# holo_clock_1_l293_rotate_90.net
KiCad netlist of a schematic drawn in EAGLE
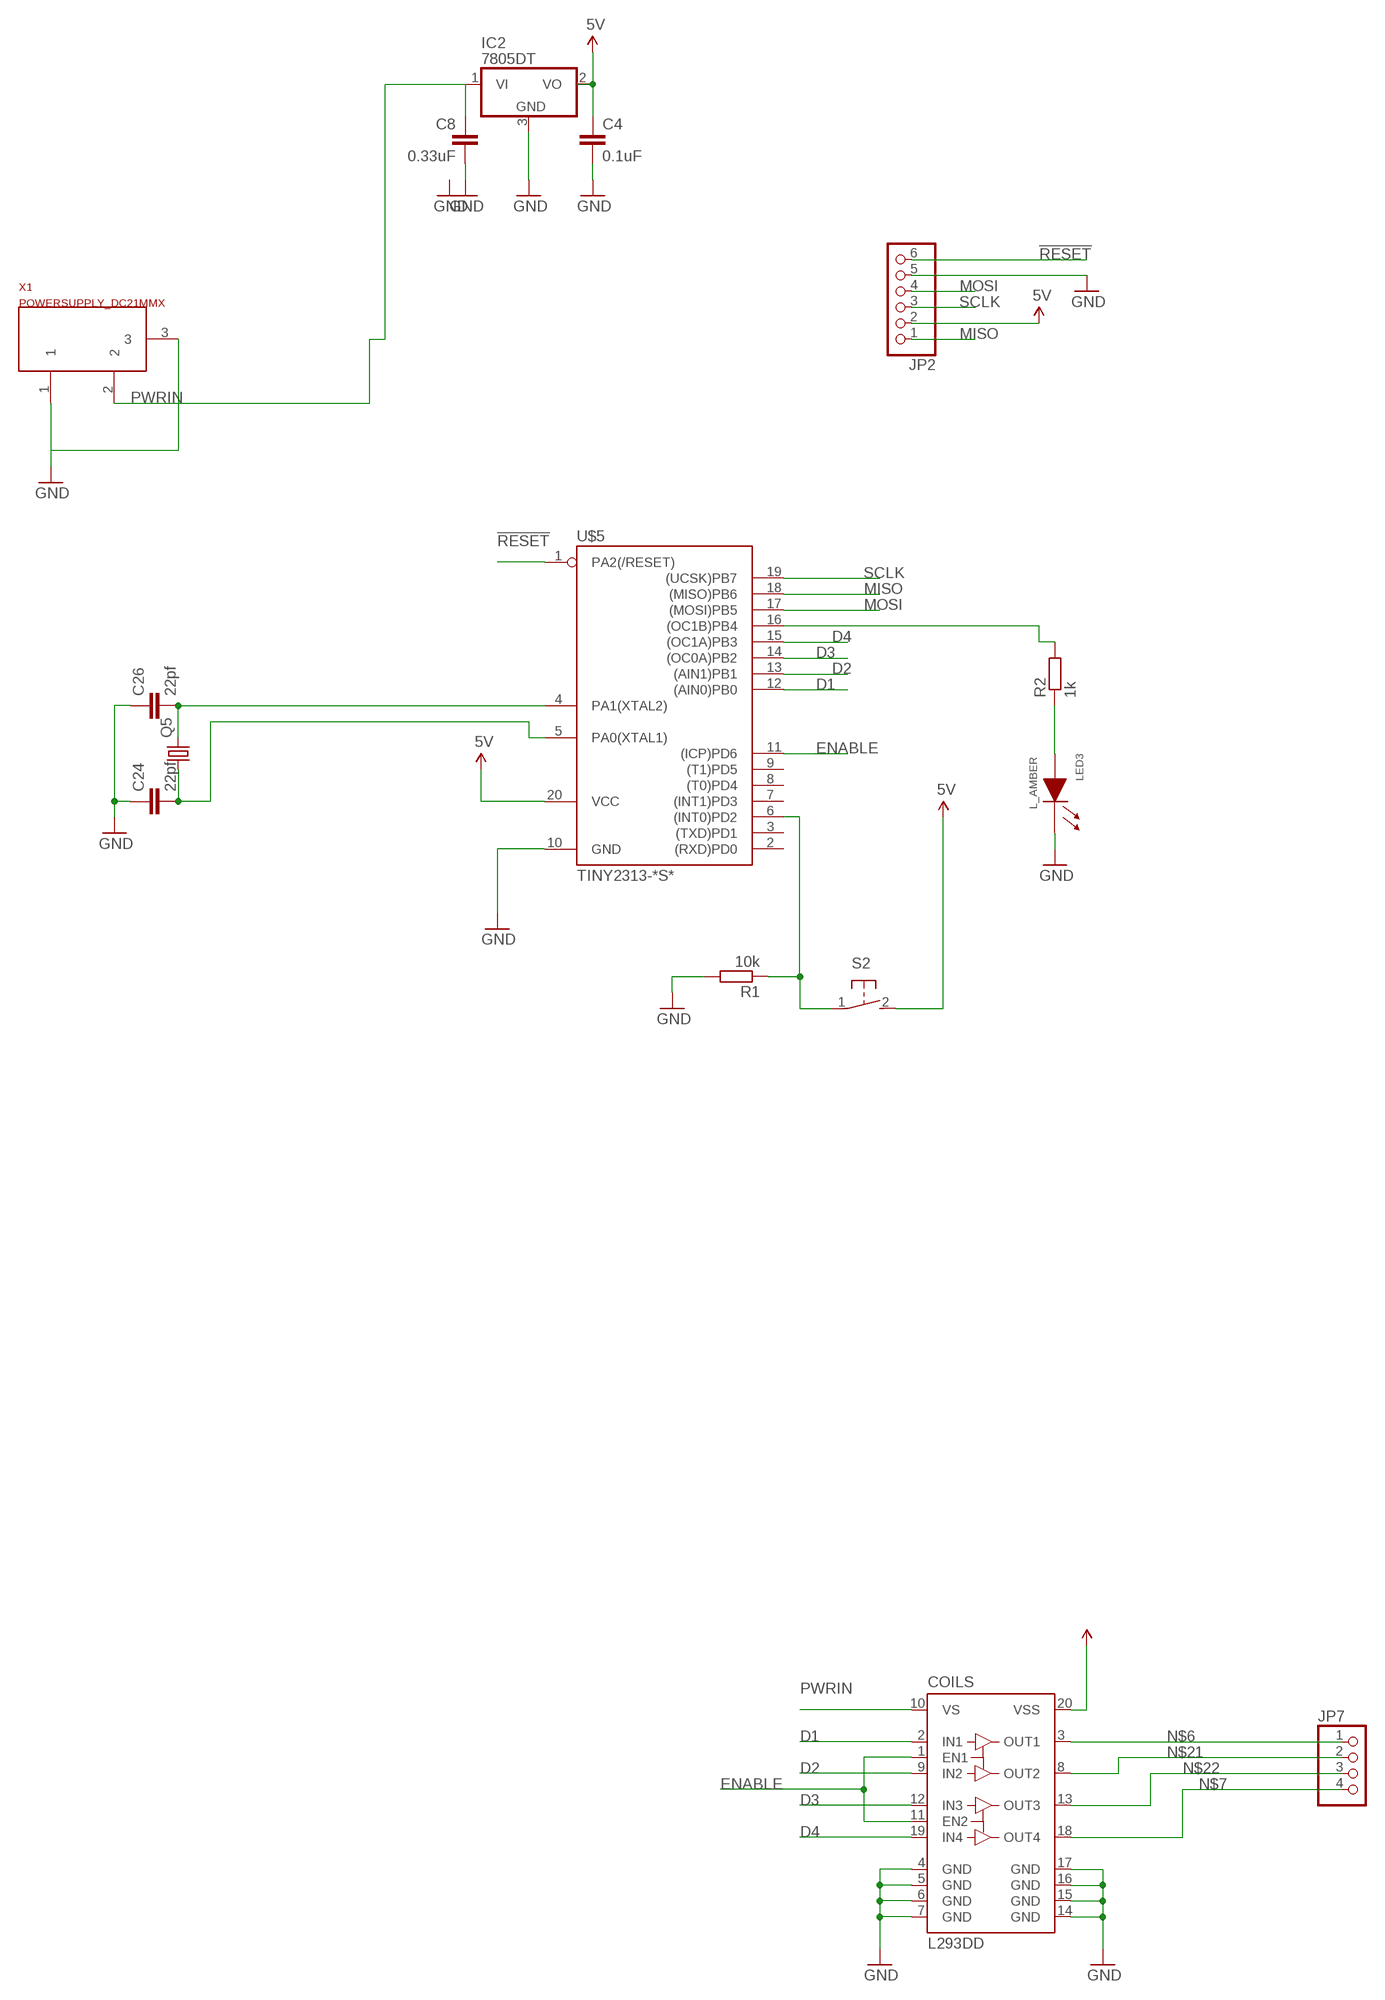
[diagram p0: schematic, sheet 1]

(export (version "E")
  (design (tool "Eeschema 10.0.6"))
  (components
    (comp (ref "C4")
      (value "0.1uF")
      (footprint "eagle-import:CAP-PTH-SMALL2")
      (libsource (lib "eagle-import") (part "CAPPTH2"))
    )
    (comp (ref "C8")
      (value "0.33uF")
      (footprint "eagle-import:CAP-PTH-SMALL2")
      (libsource (lib "eagle-import") (part "CAPPTH2"))
    )
    (comp (ref "C24")
      (value "22pf")
      (footprint "eagle-import:0805")
      (libsource (lib "eagle-import") (part "CAP0805"))
    )
    (comp (ref "C26")
      (value "22pf")
      (footprint "eagle-import:0805")
      (libsource (lib "eagle-import") (part "CAP0805"))
    )
    (comp (ref "COILS")
      (value "L293DD")
      (footprint "eagle-import:SO20")
      (libsource (lib "eagle-import") (part "L293DD"))
    )
    (comp (ref "IC2")
      (value "7805DT")
      (footprint "eagle-import:TO252")
      (libsource (lib "eagle-import") (part "78DT05"))
    )
    (comp (ref "JP2")
      (value "PINHD-1X6")
      (footprint "eagle-import:1X06")
      (libsource (lib "eagle-import") (part "PINHD-1X6"))
    )
    (comp (ref "JP7")
      (value "PINHD-1X04_2.54")
      (footprint "eagle-import:1X04")
      (libsource (lib "eagle-import") (part "PINHD-1X04_2.54"))
    )
    (comp (ref "LED3")
      (value "L_AMBER")
      (footprint "eagle-import:LED0805")
      (libsource (lib "eagle-import") (part "LED0805"))
    )
    (comp (ref "Q5")
      (value "CRYSTALHC49S")
      (footprint "eagle-import:HC49_S")
      (libsource (lib "eagle-import") (part "CRYSTALHC49S"))
    )
    (comp (ref "R1")
      (value "10k")
      (footprint "eagle-import:R0805")
      (libsource (lib "eagle-import") (part "R-EU_R0805"))
    )
    (comp (ref "R2")
      (value "1k")
      (footprint "eagle-import:R0805")
      (libsource (lib "eagle-import") (part "R-EU_R0805"))
    )
    (comp (ref "S2")
      (value "31-XX")
      (footprint "eagle-import:B3F-31XX")
      (fields (field (name "MPN") "B3F-3100"))
      (libsource (lib "eagle-import") (part "31-XX"))
    )
    (comp (ref "U$5")
      (value "TINY2313-*S*")
      (footprint "eagle-import:SO20L$")
      (libsource (lib "eagle-import") (part "TINY2313-S"))
    )
    (comp (ref "X1")
      (value "POWERSUPPLY_DC21MMX")
      (footprint "eagle-import:POWERSUPPLY_DC-21MM")
      (libsource (lib "eagle-import") (part "POWERSUPPLY_DC21MMX"))
    )
  )
  (nets
    (net (code "1") (name "/D1") (class "Default")
      (node (ref "COILS") (pin "2") (pinfunction "IN1_2") (pintype "input"))
      (node (ref "U$5") (pin "12") (pinfunction "(AIN0)PB0_12") (pintype "bidirectional"))
    )
    (net (code "2") (name "/D2") (class "Default")
      (node (ref "COILS") (pin "9") (pinfunction "IN2_9") (pintype "input"))
      (node (ref "U$5") (pin "13") (pinfunction "(AIN1)PB1_13") (pintype "bidirectional"))
    )
    (net (code "3") (name "/D3") (class "Default")
      (node (ref "COILS") (pin "12") (pinfunction "IN3_12") (pintype "input"))
      (node (ref "U$5") (pin "14") (pinfunction "(OC0A)PB2_14") (pintype "bidirectional"))
    )
    (net (code "4") (name "/D4") (class "Default")
      (node (ref "COILS") (pin "19") (pinfunction "IN4_19") (pintype "input"))
      (node (ref "U$5") (pin "15") (pinfunction "(OC1A)PB3_15") (pintype "bidirectional"))
    )
    (net (code "5") (name "/ENABLE") (class "Default")
      (node (ref "COILS") (pin "1") (pinfunction "EN1_1") (pintype "input"))
      (node (ref "COILS") (pin "11") (pinfunction "EN2_11") (pintype "input"))
      (node (ref "U$5") (pin "11") (pinfunction "(ICP)PD6_11") (pintype "bidirectional"))
    )
    (net (code "6") (name "/MISO") (class "Default")
      (node (ref "JP2") (pin "1") (pinfunction "1_1") (pintype "passive"))
      (node (ref "U$5") (pin "18") (pinfunction "(MISO)PB6_18") (pintype "bidirectional"))
    )
    (net (code "7") (name "/MOSI") (class "Default")
      (node (ref "JP2") (pin "4") (pinfunction "4_4") (pintype "passive"))
      (node (ref "U$5") (pin "17") (pinfunction "(MOSI)PB5_17") (pintype "bidirectional"))
    )
    (net (code "8") (name "/N$6") (class "Default")
      (node (ref "COILS") (pin "3") (pinfunction "OUT1_3") (pintype "output"))
      (node (ref "JP7") (pin "1") (pinfunction "1_1") (pintype "passive"))
    )
    (net (code "9") (name "/N$7") (class "Default")
      (node (ref "COILS") (pin "18") (pinfunction "OUT4_18") (pintype "output"))
      (node (ref "JP7") (pin "4") (pinfunction "4_4") (pintype "passive"))
      (node (ref "LED3") (pin "2") (pinfunction "AN_2") (pintype "passive"))
      (node (ref "R2") (pin "1") (pinfunction "1_1") (pintype "passive"))
    )
    (net (code "10") (name "/N$21") (class "Default")
      (node (ref "COILS") (pin "8") (pinfunction "OUT2_8") (pintype "output"))
      (node (ref "JP7") (pin "2") (pinfunction "2_2") (pintype "passive"))
    )
    (net (code "11") (name "/N$22") (class "Default")
      (node (ref "COILS") (pin "13") (pinfunction "OUT3_13") (pintype "output"))
      (node (ref "JP7") (pin "3") (pinfunction "3_3") (pintype "passive"))
    )
    (net (code "12") (name "/PWRIN") (class "Default")
      (node (ref "C8") (pin "1") (pinfunction "1_1") (pintype "passive"))
      (node (ref "COILS") (pin "10") (pinfunction "VS_10") (pintype "power_in"))
      (node (ref "IC2") (pin "1") (pinfunction "VI_1") (pintype "input"))
      (node (ref "X1") (pin "2") (pinfunction "2_2") (pintype "power_in"))
    )
    (net (code "13") (name "/SCLK") (class "Default")
      (node (ref "JP2") (pin "3") (pinfunction "3_3") (pintype "passive"))
      (node (ref "U$5") (pin "19") (pinfunction "(UCSK)PB7_19") (pintype "bidirectional"))
    )
    (net (code "14") (name "/~{RESET}") (class "Default")
      (node (ref "JP2") (pin "6") (pinfunction "6_6") (pintype "passive"))
      (node (ref "U$5") (pin "1") (pinfunction "PA2(/RESET)_1") (pintype "input"))
    )
    (net (code "15") (name "5V") (class "Default")
      (node (ref "C4") (pin "1") (pinfunction "1_1") (pintype "passive"))
      (node (ref "COILS") (pin "20") (pinfunction "VSS_20") (pintype "power_in"))
      (node (ref "IC2") (pin "2") (pinfunction "VO_2") (pintype "passive"))
      (node (ref "JP2") (pin "2") (pinfunction "2_2") (pintype "passive"))
      (node (ref "S2") (pin "2") (pinfunction "S_2") (pintype "passive"))
      (node (ref "U$5") (pin "20") (pinfunction "VCC_20") (pintype "power_in"))
    )
    (net (code "16") (name "GND") (class "Default")
      (node (ref "C24") (pin "1") (pinfunction "1_1") (pintype "passive"))
      (node (ref "C26") (pin "1") (pinfunction "1_1") (pintype "passive"))
      (node (ref "C4") (pin "2") (pinfunction "2_2") (pintype "passive"))
      (node (ref "C8") (pin "2") (pinfunction "2_2") (pintype "passive"))
      (node (ref "COILS") (pin "14") (pinfunction "GND_14") (pintype "power_in"))
      (node (ref "COILS") (pin "15") (pinfunction "GND_15") (pintype "power_in"))
      (node (ref "COILS") (pin "16") (pinfunction "GND_16") (pintype "power_in"))
      (node (ref "COILS") (pin "17") (pinfunction "GND_17") (pintype "power_in"))
      (node (ref "COILS") (pin "4") (pinfunction "GND_4") (pintype "power_in"))
      (node (ref "COILS") (pin "5") (pinfunction "GND_5") (pintype "power_in"))
      (node (ref "COILS") (pin "6") (pinfunction "GND_6") (pintype "power_in"))
      (node (ref "COILS") (pin "7") (pinfunction "GND_7") (pintype "power_in"))
      (node (ref "IC2") (pin "3") (pinfunction "GND_3") (pintype "passive"))
      (node (ref "JP2") (pin "5") (pinfunction "5_5") (pintype "passive"))
      (node (ref "LED3") (pin "1") (pinfunction "CA_1") (pintype "passive"))
      (node (ref "R1") (pin "2") (pinfunction "2_2") (pintype "passive"))
      (node (ref "U$5") (pin "10") (pinfunction "GND_10") (pintype "power_in"))
      (node (ref "X1") (pin "1") (pinfunction "1_1") (pintype "power_in"))
      (node (ref "X1") (pin "3") (pinfunction "3_3") (pintype "power_in"))
    )
    (net (code "17") (name "Net-(S2-P)") (class "Default")
      (node (ref "R1") (pin "1") (pinfunction "1_1") (pintype "passive"))
      (node (ref "S2") (pin "1") (pinfunction "P_1") (pintype "passive"))
      (node (ref "U$5") (pin "6") (pinfunction "(INT0)PD2_6") (pintype "bidirectional"))
    )
    (net (code "18") (name "Net-(U$5-(OC1B)PB4)") (class "Default")
      (node (ref "R2") (pin "2") (pinfunction "2_2") (pintype "passive"))
      (node (ref "U$5") (pin "16") (pinfunction "(OC1B)PB4_16") (pintype "bidirectional"))
    )
    (net (code "19") (name "Net-(U$5-PA0(XTAL1))") (class "Default")
      (node (ref "C24") (pin "2") (pinfunction "2_2") (pintype "passive"))
      (node (ref "Q5") (pin "1") (pinfunction "1_1") (pintype "passive"))
      (node (ref "U$5") (pin "5") (pinfunction "PA0(XTAL1)_5") (pintype "bidirectional"))
    )
    (net (code "20") (name "Net-(U$5-PA1(XTAL2))") (class "Default")
      (node (ref "C26") (pin "2") (pinfunction "2_2") (pintype "passive"))
      (node (ref "Q5") (pin "2") (pinfunction "2_2") (pintype "passive"))
      (node (ref "U$5") (pin "4") (pinfunction "PA1(XTAL2)_4") (pintype "bidirectional"))
    )
    (net (code "21") (name "unconnected-(U$5-(INT1)PD3-Pad7)") (class "Default")
      (node (ref "U$5") (pin "7") (pinfunction "(INT1)PD3_7") (pintype "bidirectional"))
    )
    (net (code "22") (name "unconnected-(U$5-(RXD)PD0-Pad2)") (class "Default")
      (node (ref "U$5") (pin "2") (pinfunction "(RXD)PD0_2") (pintype "bidirectional"))
    )
    (net (code "23") (name "unconnected-(U$5-(T0)PD4-Pad8)") (class "Default")
      (node (ref "U$5") (pin "8") (pinfunction "(T0)PD4_8") (pintype "bidirectional"))
    )
    (net (code "24") (name "unconnected-(U$5-(T1)PD5-Pad9)") (class "Default")
      (node (ref "U$5") (pin "9") (pinfunction "(T1)PD5_9") (pintype "bidirectional"))
    )
    (net (code "25") (name "unconnected-(U$5-(TXD)PD1-Pad3)") (class "Default")
      (node (ref "U$5") (pin "3") (pinfunction "(TXD)PD1_3") (pintype "bidirectional"))
    )
  )
)
